# FDevT.net
KiCad netlist of a schematic drawn in EAGLE
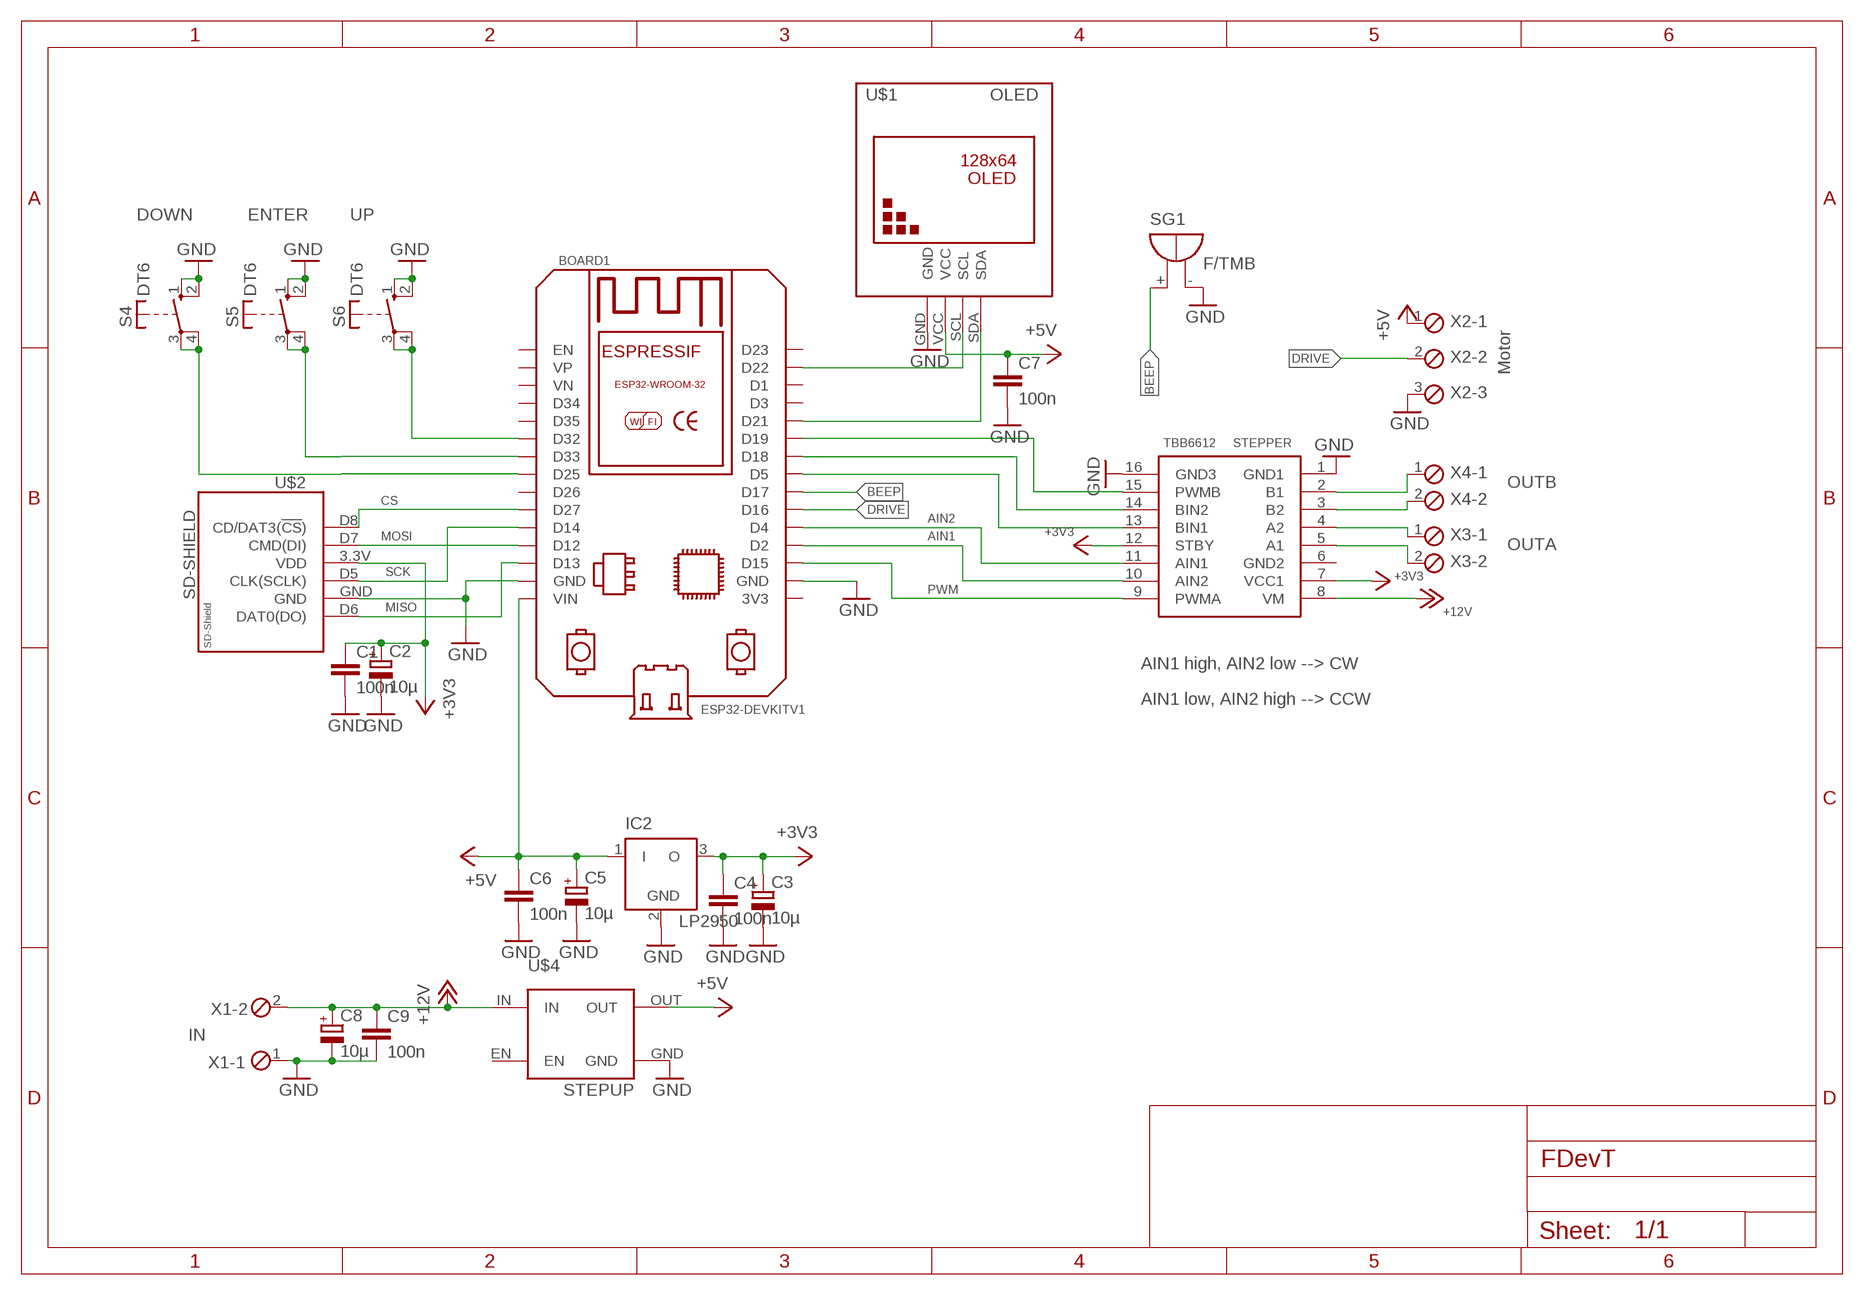
[diagram p0: schematic, sheet 1]

(export (version "E")
  (design (tool "Eeschema 10.0.6"))
  (components
    (comp (ref "BOARD1")
      (value "ESP32DEVKITV1")
      (footprint "eagle-import:ESP32-DEVKITV1")
      (libsource (lib "eagle-import") (part "ESP32DEVKITV1"))
    )
    (comp (ref "C1")
      (value "100n")
      (footprint "eagle-import:C0805")
      (libsource (lib "eagle-import") (part "C-EUC0805"))
    )
    (comp (ref "C2")
      (value "10µ")
      (footprint "eagle-import:SMC_B")
      (libsource (lib "eagle-import") (part "CPOL-EUSMCB"))
    )
    (comp (ref "C3")
      (value "10µ")
      (footprint "eagle-import:SMC_B")
      (libsource (lib "eagle-import") (part "CPOL-EUSMCB"))
    )
    (comp (ref "C4")
      (value "100n")
      (footprint "eagle-import:C0805")
      (libsource (lib "eagle-import") (part "C-EUC0805"))
    )
    (comp (ref "C5")
      (value "10µ")
      (footprint "eagle-import:SMC_B")
      (libsource (lib "eagle-import") (part "CPOL-EUSMCB"))
    )
    (comp (ref "C6")
      (value "100n")
      (footprint "eagle-import:C0805")
      (libsource (lib "eagle-import") (part "C-EUC0805"))
    )
    (comp (ref "C7")
      (value "100n")
      (footprint "eagle-import:C0805")
      (libsource (lib "eagle-import") (part "C-EUC0805"))
    )
    (comp (ref "C8")
      (value "10µ")
      (footprint "eagle-import:SMC_B")
      (libsource (lib "eagle-import") (part "CPOL-EUSMCB"))
    )
    (comp (ref "C9")
      (value "100n")
      (footprint "eagle-import:C0805")
      (libsource (lib "eagle-import") (part "C-EUC0805"))
    )
    (comp (ref "IC2")
      (value "LP2950")
      (footprint "eagle-import:DPACK")
      (libsource (lib "eagle-import") (part "LP2950"))
    )
    (comp (ref "S4")
      (value "DT6")
      (footprint "eagle-import:DT6")
      (libsource (lib "eagle-import") (part "DT6"))
    )
    (comp (ref "S5")
      (value "DT6")
      (footprint "eagle-import:DT6")
      (libsource (lib "eagle-import") (part "DT6"))
    )
    (comp (ref "S6")
      (value "DT6")
      (footprint "eagle-import:DT6")
      (libsource (lib "eagle-import") (part "DT6"))
    )
    (comp (ref "SG1")
      (value "F/TMB")
      (footprint "eagle-import:F_TMB")
      (libsource (lib "eagle-import") (part "F/TMB"))
    )
    (comp (ref "STEPPER")
      (value "TBB6612")
      (footprint "eagle-import:DRIVER")
      (libsource (lib "eagle-import") (part "TBB6612"))
    )
    (comp (ref "U$1")
      (value "OLED")
      (footprint "eagle-import:SIP")
      (libsource (lib "eagle-import") (part "OLED"))
    )
    (comp (ref "U$2")
      (value "SD-SHIELD")
      (footprint "eagle-import:SD_SHIELD")
      (libsource (lib "eagle-import") (part "SD-SHIELD"))
    )
    (comp (ref "U$4")
      (value "STEPUP")
      (footprint "eagle-import:STEPUP")
      (libsource (lib "eagle-import") (part "STEPUP"))
    )
    (comp (ref "X1")
      (value "IN")
      (footprint "eagle-import:2POL254")
      (libsource (lib "eagle-import") (part "MPT2"))
    )
    (comp (ref "X2")
      (value "Motor")
      (footprint "eagle-import:3POL254")
      (libsource (lib "eagle-import") (part "MPT3"))
    )
    (comp (ref "X3")
      (value "OUTA")
      (footprint "eagle-import:2POL254")
      (libsource (lib "eagle-import") (part "MPT2"))
    )
    (comp (ref "X4")
      (value "OUTB")
      (footprint "eagle-import:2POL254")
      (libsource (lib "eagle-import") (part "MPT2"))
    )
  )
  (nets
    (net (code "1") (name "+3V3") (class "Default")
      (node (ref "C1") (pin "1") (pinfunction "1_1") (pintype "passive"))
      (node (ref "C2") (pin "+") (pinfunction "+_+") (pintype "passive"))
      (node (ref "C3") (pin "+") (pinfunction "+_+") (pintype "passive"))
      (node (ref "C4") (pin "1") (pinfunction "1_1") (pintype "passive"))
      (node (ref "IC2") (pin "3") (pinfunction "O_3") (pintype "input"))
      (node (ref "STEPPER") (pin "12") (pinfunction "STBY_12") (pintype "bidirectional"))
      (node (ref "STEPPER") (pin "7") (pinfunction "VCC1_7") (pintype "bidirectional"))
      (node (ref "U$2") (pin "3.3V") (pinfunction "VDD_3.3V") (pintype "power_in"))
    )
    (net (code "2") (name "+5V") (class "Default")
      (node (ref "BOARD1") (pin "VIN") (pinfunction "VIN_VIN") (pintype "bidirectional"))
      (node (ref "C5") (pin "+") (pinfunction "+_+") (pintype "passive"))
      (node (ref "C6") (pin "1") (pinfunction "1_1") (pintype "passive"))
      (node (ref "C7") (pin "1") (pinfunction "1_1") (pintype "passive"))
      (node (ref "IC2") (pin "1") (pinfunction "I_1") (pintype "input"))
      (node (ref "U$1") (pin "VCC") (pinfunction "VCC_VCC") (pintype "bidirectional"))
      (node (ref "U$4") (pin "OUT") (pinfunction "OUT_OUT") (pintype "bidirectional"))
      (node (ref "X2") (pin "1") (pinfunction "1_1") (pintype "passive"))
    )
    (net (code "3") (name "+12V") (class "Default")
      (node (ref "C8") (pin "+") (pinfunction "+_+") (pintype "passive"))
      (node (ref "C9") (pin "1") (pinfunction "1_1") (pintype "passive"))
      (node (ref "STEPPER") (pin "8") (pinfunction "VM_8") (pintype "bidirectional"))
      (node (ref "U$4") (pin "IN") (pinfunction "IN_IN") (pintype "bidirectional"))
      (node (ref "X1") (pin "2") (pinfunction "1_2") (pintype "passive"))
    )
    (net (code "4") (name "/AIN1") (class "Default")
      (node (ref "BOARD1") (pin "D2") (pinfunction "D2_D2") (pintype "bidirectional"))
      (node (ref "STEPPER") (pin "10") (pinfunction "AIN2_10") (pintype "bidirectional"))
    )
    (net (code "5") (name "/AIN2") (class "Default")
      (node (ref "BOARD1") (pin "D4") (pinfunction "D4_D4") (pintype "bidirectional"))
      (node (ref "STEPPER") (pin "11") (pinfunction "AIN1_11") (pintype "bidirectional"))
    )
    (net (code "6") (name "/CS") (class "Default")
      (node (ref "BOARD1") (pin "D27") (pinfunction "D27_D27") (pintype "bidirectional"))
      (node (ref "U$2") (pin "D8") (pinfunction "CD/DAT3(~{CS})_D8") (pintype "bidirectional"))
    )
    (net (code "7") (name "/DOWN") (class "Default")
      (node (ref "BOARD1") (pin "D25") (pinfunction "D25_D25") (pintype "bidirectional"))
      (node (ref "S4") (pin "3") (pinfunction "P_3") (pintype "passive"))
      (node (ref "S4") (pin "4") (pinfunction "P_4") (pintype "passive"))
    )
    (net (code "8") (name "/ENTER") (class "Default")
      (node (ref "BOARD1") (pin "D33") (pinfunction "D33_D33") (pintype "bidirectional"))
      (node (ref "S5") (pin "3") (pinfunction "P_3") (pintype "passive"))
      (node (ref "S5") (pin "4") (pinfunction "P_4") (pintype "passive"))
    )
    (net (code "9") (name "/MISO") (class "Default")
      (node (ref "BOARD1") (pin "D13") (pinfunction "D13_D13") (pintype "bidirectional"))
      (node (ref "U$2") (pin "D6") (pinfunction "DAT0(DO)_D6") (pintype "bidirectional"))
    )
    (net (code "10") (name "/MOSI") (class "Default")
      (node (ref "BOARD1") (pin "D12") (pinfunction "D12_D12") (pintype "bidirectional"))
      (node (ref "U$2") (pin "D7") (pinfunction "CMD(DI)_D7") (pintype "bidirectional"))
    )
    (net (code "11") (name "/PWM") (class "Default")
      (node (ref "BOARD1") (pin "D15") (pinfunction "D15_D15") (pintype "bidirectional"))
      (node (ref "STEPPER") (pin "9") (pinfunction "PWMA_9") (pintype "bidirectional"))
    )
    (net (code "12") (name "/SCK") (class "Default")
      (node (ref "BOARD1") (pin "D14") (pinfunction "D14_D14") (pintype "bidirectional"))
      (node (ref "U$2") (pin "D5") (pinfunction "CLK(SCLK)_D5") (pintype "input"))
    )
    (net (code "13") (name "/UP") (class "Default")
      (node (ref "BOARD1") (pin "D32") (pinfunction "D32_D32") (pintype "bidirectional"))
      (node (ref "S6") (pin "3") (pinfunction "P_3") (pintype "passive"))
      (node (ref "S6") (pin "4") (pinfunction "P_4") (pintype "passive"))
    )
    (net (code "14") (name "BEEP") (class "Default")
      (node (ref "BOARD1") (pin "D17") (pinfunction "D17_D17") (pintype "bidirectional"))
      (node (ref "SG1") (pin "+") (pinfunction "+_+") (pintype "passive"))
    )
    (net (code "15") (name "DRIVE") (class "Default")
      (node (ref "BOARD1") (pin "D16") (pinfunction "D16_D16") (pintype "bidirectional"))
      (node (ref "X2") (pin "2") (pinfunction "1_2") (pintype "passive"))
    )
    (net (code "16") (name "GND") (class "Default")
      (node (ref "BOARD1") (pin "GND") (pinfunction "GND_GND") (pintype "bidirectional"))
      (node (ref "BOARD1") (pin "GND@1") (pinfunction "GND_GND@1") (pintype "bidirectional"))
      (node (ref "C1") (pin "2") (pinfunction "2_2") (pintype "passive"))
      (node (ref "C2") (pin "-") (pinfunction "-_-") (pintype "passive"))
      (node (ref "C3") (pin "-") (pinfunction "-_-") (pintype "passive"))
      (node (ref "C4") (pin "2") (pinfunction "2_2") (pintype "passive"))
      (node (ref "C5") (pin "-") (pinfunction "-_-") (pintype "passive"))
      (node (ref "C6") (pin "2") (pinfunction "2_2") (pintype "passive"))
      (node (ref "C7") (pin "2") (pinfunction "2_2") (pintype "passive"))
      (node (ref "C8") (pin "-") (pinfunction "-_-") (pintype "passive"))
      (node (ref "C9") (pin "2") (pinfunction "2_2") (pintype "passive"))
      (node (ref "IC2") (pin "2") (pinfunction "GND_2") (pintype "power_in"))
      (node (ref "S4") (pin "1") (pinfunction "S_1") (pintype "passive"))
      (node (ref "S4") (pin "2") (pinfunction "S_2") (pintype "passive"))
      (node (ref "S5") (pin "1") (pinfunction "S_1") (pintype "passive"))
      (node (ref "S5") (pin "2") (pinfunction "S_2") (pintype "passive"))
      (node (ref "S6") (pin "1") (pinfunction "S_1") (pintype "passive"))
      (node (ref "S6") (pin "2") (pinfunction "S_2") (pintype "passive"))
      (node (ref "SG1") (pin "-") (pinfunction "-_-") (pintype "passive"))
      (node (ref "STEPPER") (pin "1") (pinfunction "GND1_1") (pintype "bidirectional"))
      (node (ref "STEPPER") (pin "16") (pinfunction "GND3_16") (pintype "bidirectional"))
      (node (ref "U$1") (pin "GND") (pinfunction "GND_GND") (pintype "bidirectional"))
      (node (ref "U$2") (pin "GND") (pinfunction "GND_GND") (pintype "power_in"))
      (node (ref "U$4") (pin "GND") (pinfunction "GND_GND") (pintype "bidirectional"))
      (node (ref "X1") (pin "1") (pinfunction "1_1") (pintype "passive"))
      (node (ref "X2") (pin "3") (pinfunction "1_3") (pintype "passive"))
    )
    (net (code "17") (name "Net-(BOARD1-PadD21)") (class "Default")
      (node (ref "BOARD1") (pin "D21") (pinfunction "D21_D21") (pintype "bidirectional"))
      (node (ref "U$1") (pin "SDA") (pinfunction "SDA_SDA") (pintype "bidirectional"))
    )
    (net (code "18") (name "Net-(BOARD1-PadD22)") (class "Default")
      (node (ref "BOARD1") (pin "D22") (pinfunction "D22_D22") (pintype "bidirectional"))
      (node (ref "U$1") (pin "SCL") (pinfunction "SCL_SCL") (pintype "bidirectional"))
    )
    (net (code "19") (name "Net-(STEPPER-A1)") (class "Default")
      (node (ref "STEPPER") (pin "5") (pinfunction "A1_5") (pintype "bidirectional"))
      (node (ref "X3") (pin "2") (pinfunction "1_2") (pintype "passive"))
    )
    (net (code "20") (name "Net-(STEPPER-A2)") (class "Default")
      (node (ref "STEPPER") (pin "4") (pinfunction "A2_4") (pintype "bidirectional"))
      (node (ref "X3") (pin "1") (pinfunction "1_1") (pintype "passive"))
    )
    (net (code "21") (name "Net-(STEPPER-B1)") (class "Default")
      (node (ref "STEPPER") (pin "2") (pinfunction "B1_2") (pintype "bidirectional"))
      (node (ref "X4") (pin "1") (pinfunction "1_1") (pintype "passive"))
    )
    (net (code "22") (name "Net-(STEPPER-B2)") (class "Default")
      (node (ref "STEPPER") (pin "3") (pinfunction "B2_3") (pintype "bidirectional"))
      (node (ref "X4") (pin "2") (pinfunction "1_2") (pintype "passive"))
    )
    (net (code "23") (name "Net-(STEPPER-BIN1)") (class "Default")
      (node (ref "BOARD1") (pin "D5") (pinfunction "D5_D5") (pintype "bidirectional"))
      (node (ref "STEPPER") (pin "13") (pinfunction "BIN1_13") (pintype "bidirectional"))
    )
    (net (code "24") (name "Net-(STEPPER-BIN2)") (class "Default")
      (node (ref "BOARD1") (pin "D18") (pinfunction "D18_D18") (pintype "bidirectional"))
      (node (ref "STEPPER") (pin "14") (pinfunction "BIN2_14") (pintype "bidirectional"))
    )
    (net (code "25") (name "Net-(STEPPER-PWMB)") (class "Default")
      (node (ref "BOARD1") (pin "D19") (pinfunction "D19_D19") (pintype "bidirectional"))
      (node (ref "STEPPER") (pin "15") (pinfunction "PWMB_15") (pintype "bidirectional"))
    )
    (net (code "26") (name "unconnected-(BOARD1-Pad3V3)") (class "Default")
      (node (ref "BOARD1") (pin "3V3") (pinfunction "3V3_3V3") (pintype "bidirectional"))
    )
    (net (code "27") (name "unconnected-(BOARD1-PadD1)") (class "Default")
      (node (ref "BOARD1") (pin "D1") (pinfunction "D1_D1") (pintype "bidirectional"))
    )
    (net (code "28") (name "unconnected-(BOARD1-PadD3)") (class "Default")
      (node (ref "BOARD1") (pin "D3") (pinfunction "D3_D3") (pintype "bidirectional"))
    )
    (net (code "29") (name "unconnected-(BOARD1-PadD23)") (class "Default")
      (node (ref "BOARD1") (pin "D23") (pinfunction "D23_D23") (pintype "bidirectional"))
    )
    (net (code "30") (name "unconnected-(BOARD1-PadD26)") (class "Default")
      (node (ref "BOARD1") (pin "D26") (pinfunction "D26_D26") (pintype "bidirectional"))
    )
    (net (code "31") (name "unconnected-(BOARD1-PadD34)") (class "Default")
      (node (ref "BOARD1") (pin "D34") (pinfunction "D34_D34") (pintype "bidirectional"))
    )
    (net (code "32") (name "unconnected-(BOARD1-PadD35)") (class "Default")
      (node (ref "BOARD1") (pin "D35") (pinfunction "D35_D35") (pintype "bidirectional"))
    )
    (net (code "33") (name "unconnected-(BOARD1-PadEN)") (class "Default")
      (node (ref "BOARD1") (pin "EN") (pinfunction "EN_EN") (pintype "bidirectional"))
    )
    (net (code "34") (name "unconnected-(BOARD1-PadVN)") (class "Default")
      (node (ref "BOARD1") (pin "VN") (pinfunction "VN_VN") (pintype "bidirectional"))
    )
    (net (code "35") (name "unconnected-(BOARD1-PadVP)") (class "Default")
      (node (ref "BOARD1") (pin "VP") (pinfunction "VP_VP") (pintype "bidirectional"))
    )
    (net (code "36") (name "unconnected-(STEPPER-GND2-Pad6)") (class "Default")
      (node (ref "STEPPER") (pin "6") (pinfunction "GND2_6") (pintype "bidirectional"))
    )
    (net (code "37") (name "unconnected-(U$4-PadEN)") (class "Default")
      (node (ref "U$4") (pin "EN") (pinfunction "EN_EN") (pintype "bidirectional"))
    )
  )
)
